# 7s_BMS_V1-1.net
KiCad netlist of a schematic drawn in EAGLE
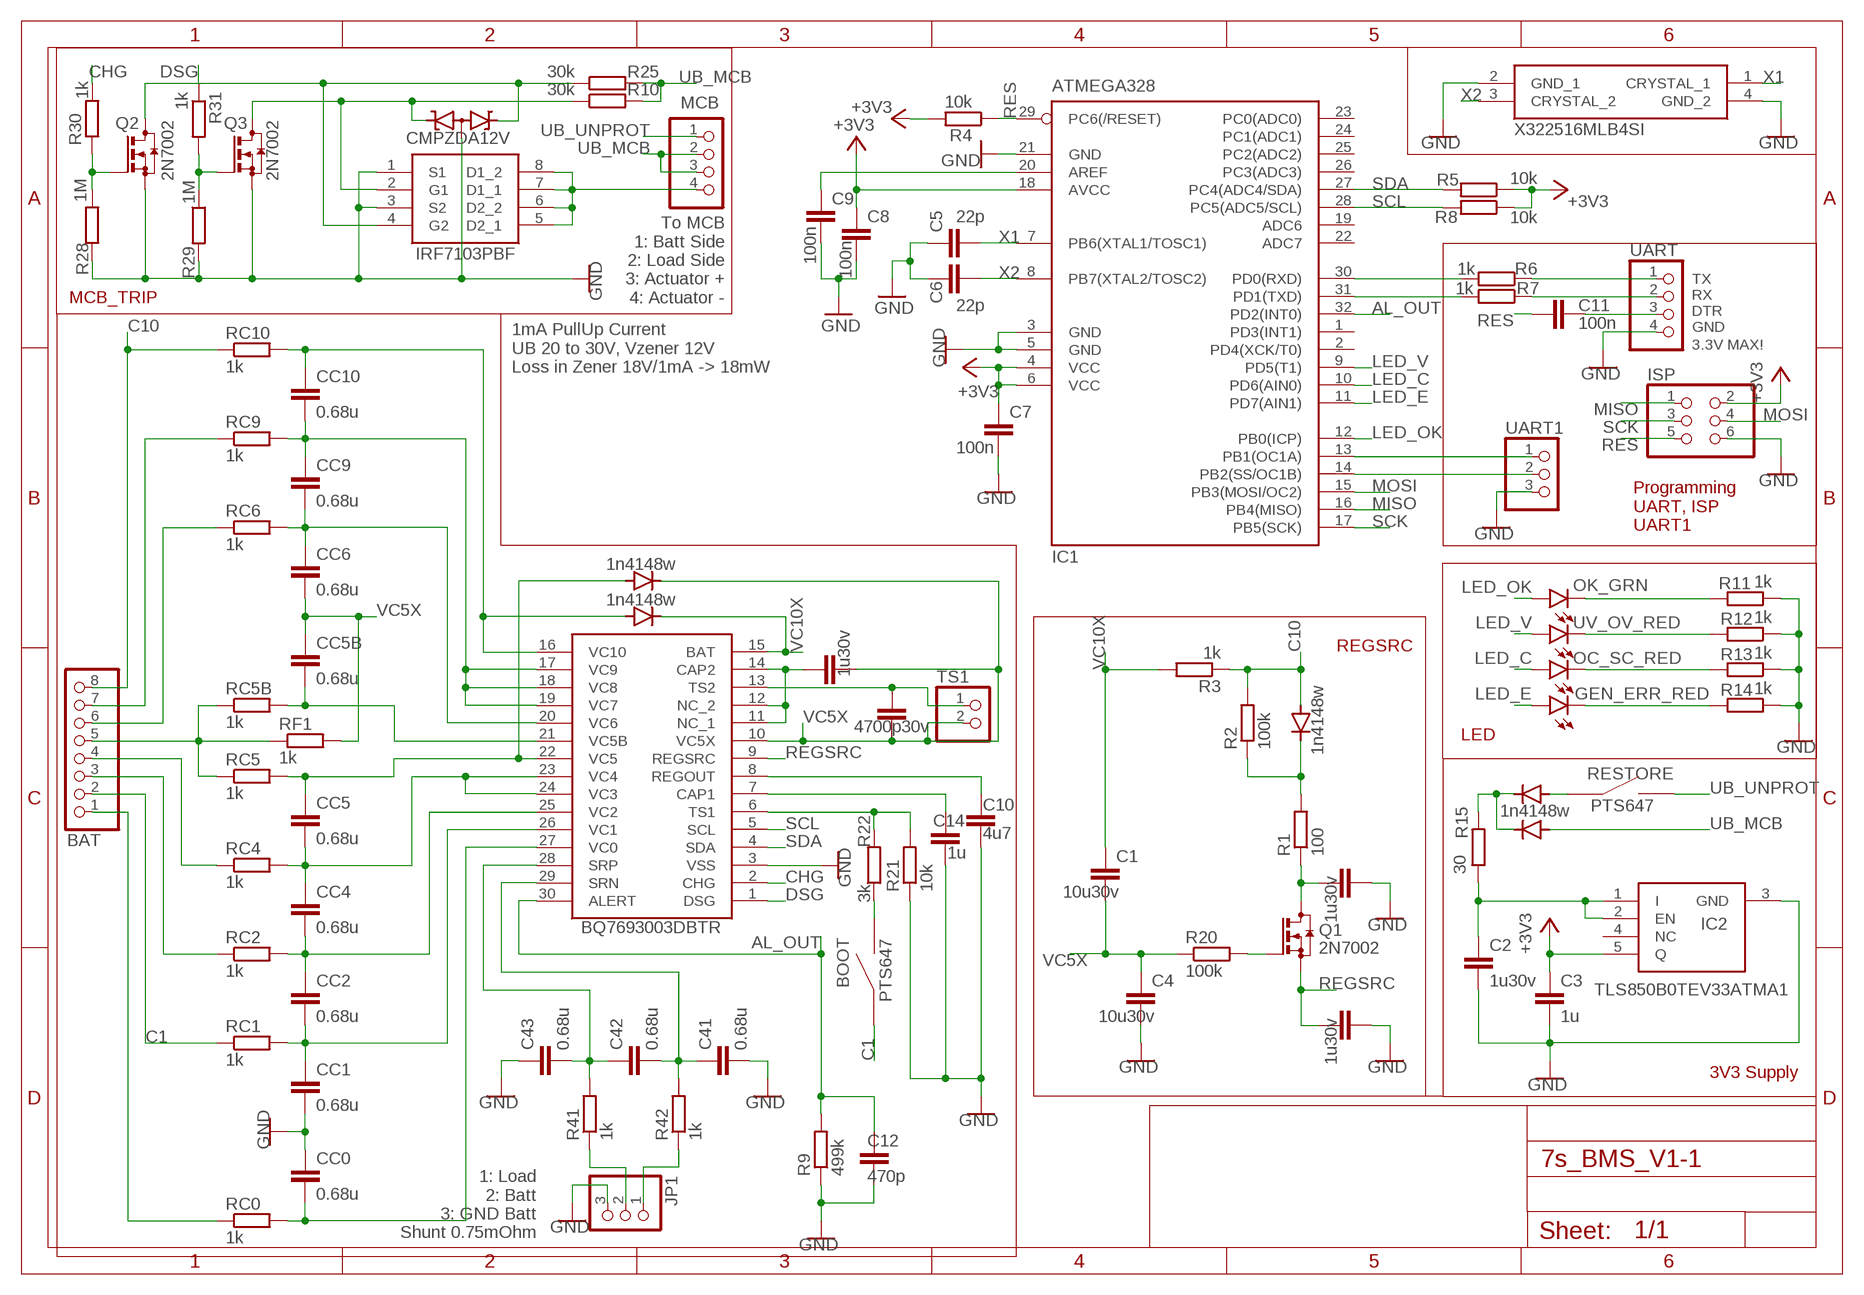
[diagram p0: schematic, sheet 1]

(export (version "E")
  (design (tool "Eeschema 10.0.6"))
  (components
    (comp (ref "BAT")
      (value "PINHD-1X8/90")
      (footprint "eagle-import:1X08_90")
      (libsource (lib "eagle-import") (part "PINHD-1X8/90"))
    )
    (comp (ref "C1")
      (value "10u30v")
      (footprint "eagle-import:C0805")
      (libsource (lib "eagle-import") (part "C-EUC0805"))
    )
    (comp (ref "C2")
      (value "1u30v")
      (footprint "eagle-import:C0805")
      (libsource (lib "eagle-import") (part "C-EUC0805"))
    )
    (comp (ref "C3")
      (value "1u")
      (footprint "eagle-import:C0603")
      (libsource (lib "eagle-import") (part "C-EUC0603"))
    )
    (comp (ref "C4")
      (value "10u30v")
      (footprint "eagle-import:C0805")
      (libsource (lib "eagle-import") (part "C-EUC0805"))
    )
    (comp (ref "C5")
      (value "22p")
      (footprint "eagle-import:C0603")
      (libsource (lib "eagle-import") (part "C-EUC0603"))
    )
    (comp (ref "C6")
      (value "22p")
      (footprint "eagle-import:C0603")
      (libsource (lib "eagle-import") (part "C-EUC0603"))
    )
    (comp (ref "C7")
      (value "100n")
      (footprint "eagle-import:C0603")
      (libsource (lib "eagle-import") (part "C-EUC0603"))
    )
    (comp (ref "C8")
      (value "100n")
      (footprint "eagle-import:C0603")
      (libsource (lib "eagle-import") (part "C-EUC0603"))
    )
    (comp (ref "C9")
      (value "100n")
      (footprint "eagle-import:C0603")
      (libsource (lib "eagle-import") (part "C-EUC0603"))
    )
    (comp (ref "C10")
      (value "4u7")
      (footprint "eagle-import:C0805")
      (libsource (lib "eagle-import") (part "C-EUC0805"))
    )
    (comp (ref "C11")
      (value "100n")
      (footprint "eagle-import:C0603")
      (libsource (lib "eagle-import") (part "C-EUC0603"))
    )
    (comp (ref "C12")
      (value "470p")
      (footprint "eagle-import:C0603")
      (libsource (lib "eagle-import") (part "C-EUC0603"))
    )
    (comp (ref "C14")
      (value "1u")
      (footprint "eagle-import:C0603")
      (libsource (lib "eagle-import") (part "C-EUC0603"))
    )
    (comp (ref "C30")
      (value "1u30v")
      (footprint "eagle-import:C0603")
      (libsource (lib "eagle-import") (part "C-EUC0603"))
    )
    (comp (ref "C31")
      (value "1u30v")
      (footprint "eagle-import:C0603")
      (libsource (lib "eagle-import") (part "C-EUC0603"))
    )
    (comp (ref "C41")
      (value "0.68u")
      (footprint "eagle-import:C0603")
      (libsource (lib "eagle-import") (part "C-EUC0603"))
    )
    (comp (ref "C42")
      (value "0.68u")
      (footprint "eagle-import:C0603")
      (libsource (lib "eagle-import") (part "C-EUC0603"))
    )
    (comp (ref "C43")
      (value "0.68u")
      (footprint "eagle-import:C0603")
      (libsource (lib "eagle-import") (part "C-EUC0603"))
    )
    (comp (ref "C61")
      (value "1u30v")
      (footprint "eagle-import:C0603")
      (libsource (lib "eagle-import") (part "C-EUC0603"))
    )
    (comp (ref "C62")
      (value "4700p30v")
      (footprint "eagle-import:C0603")
      (libsource (lib "eagle-import") (part "C-EUC0603"))
    )
    (comp (ref "CC0")
      (value "0.68u")
      (footprint "eagle-import:C0603")
      (libsource (lib "eagle-import") (part "C-EUC0603"))
    )
    (comp (ref "CC1")
      (value "0.68u")
      (footprint "eagle-import:C0603")
      (libsource (lib "eagle-import") (part "C-EUC0603"))
    )
    (comp (ref "CC2")
      (value "0.68u")
      (footprint "eagle-import:C0603")
      (libsource (lib "eagle-import") (part "C-EUC0603"))
    )
    (comp (ref "CC4")
      (value "0.68u")
      (footprint "eagle-import:C0603")
      (libsource (lib "eagle-import") (part "C-EUC0603"))
    )
    (comp (ref "CC5")
      (value "0.68u")
      (footprint "eagle-import:C0603")
      (libsource (lib "eagle-import") (part "C-EUC0603"))
    )
    (comp (ref "CC5B")
      (value "0.68u")
      (footprint "eagle-import:C0603")
      (libsource (lib "eagle-import") (part "C-EUC0603"))
    )
    (comp (ref "CC6")
      (value "0.68u")
      (footprint "eagle-import:C0603")
      (libsource (lib "eagle-import") (part "C-EUC0603"))
    )
    (comp (ref "CC9")
      (value "0.68u")
      (footprint "eagle-import:C0603")
      (libsource (lib "eagle-import") (part "C-EUC0603"))
    )
    (comp (ref "CC10")
      (value "0.68u")
      (footprint "eagle-import:C0603")
      (libsource (lib "eagle-import") (part "C-EUC0603"))
    )
    (comp (ref "D1")
      (value "1n4148w")
      (footprint "eagle-import:SOD123")
      (libsource (lib "eagle-import") (part "DIODE-SOD123"))
    )
    (comp (ref "D2")
      (value "1n4148w")
      (footprint "eagle-import:SOD123")
      (libsource (lib "eagle-import") (part "DIODE-SOD123"))
    )
    (comp (ref "D3")
      (value "1n4148w")
      (footprint "eagle-import:SOD123")
      (libsource (lib "eagle-import") (part "DIODE-SOD123"))
    )
    (comp (ref "D4")
      (value "1n4148w")
      (footprint "eagle-import:SOD123")
      (libsource (lib "eagle-import") (part "DIODE-SOD123"))
    )
    (comp (ref "D5")
      (value "1n4148w")
      (footprint "eagle-import:SOD123")
      (libsource (lib "eagle-import") (part "DIODE-SOD123"))
    )
    (comp (ref "GEN_ERR_RED")
      (value "KT-0603R")
      (footprint "eagle-import:CHIP-LED0603")
      (libsource (lib "eagle-import") (part "LEDCHIP-LED0603"))
    )
    (comp (ref "IC1")
      (value "ATMEGA328")
      (footprint "eagle-import:TQFP32-08")
      (fields (field (name "MPN") "ATMEGA8-16AU"))
      (libsource (lib "eagle-import") (part "MEGA8-AI"))
    )
    (comp (ref "IC2")
      (value "TLS850B0TEV33ATMA1")
      (footprint "eagle-import:BTS6143D")
      (fields (field (name "MOUSER_PART_NUMBER") "726-TLS850B0TEV33ATM"))
      (libsource (lib "eagle-import") (part "TLS850B0TEV33ATMA1"))
    )
    (comp (ref "IC3")
      (value "BQ7693003DBTR")
      (footprint "eagle-import:SOP50P640X120-30N")
      (fields (field (name "MOUSER_PART_NUMBER") "595-BQ7693003DBTR"))
      (libsource (lib "eagle-import") (part "BQ7693003DBTR"))
    )
    (comp (ref "ISP")
      (value "PINHD-2X3")
      (footprint "eagle-import:2X03")
      (libsource (lib "eagle-import") (part "PINHD-2X3"))
    )
    (comp (ref "JP1")
      (value "PINHD-1X3/90")
      (footprint "eagle-import:1X03_90")
      (libsource (lib "eagle-import") (part "PINHD-1X3/90"))
    )
    (comp (ref "MCB")
      (value "PINHD-1X4")
      (footprint "eagle-import:1X04")
      (libsource (lib "eagle-import") (part "PINHD-1X4"))
    )
    (comp (ref "OC_SC_RED")
      (value "KT-0603R")
      (footprint "eagle-import:CHIP-LED0603")
      (libsource (lib "eagle-import") (part "LEDCHIP-LED0603"))
    )
    (comp (ref "OK_GRN")
      (value "19-217/GHC-YR1S2/3T")
      (footprint "eagle-import:CHIP-LED0603")
      (libsource (lib "eagle-import") (part "LEDCHIP-LED0603"))
    )
    (comp (ref "Q1")
      (value "2N7002")
      (footprint "eagle-import:SOT23")
      (libsource (lib "eagle-import") (part "BSS123"))
    )
    (comp (ref "Q2")
      (value "2N7002")
      (footprint "eagle-import:SOT23")
      (libsource (lib "eagle-import") (part "BSS123"))
    )
    (comp (ref "Q3")
      (value "2N7002")
      (footprint "eagle-import:SOT23")
      (libsource (lib "eagle-import") (part "BSS123"))
    )
    (comp (ref "Q4")
      (value "IRF7103PBF")
      (footprint "eagle-import:SOIC127P600X175-8N")
      (libsource (lib "eagle-import") (part "IRF7103PBF"))
    )
    (comp (ref "R1")
      (value "100")
      (footprint "eagle-import:R0603")
      (libsource (lib "eagle-import") (part "R-EU_R0603"))
    )
    (comp (ref "R2")
      (value "100k")
      (footprint "eagle-import:R0603")
      (libsource (lib "eagle-import") (part "R-EU_R0603"))
    )
    (comp (ref "R3")
      (value "1k")
      (footprint "eagle-import:R0603")
      (libsource (lib "eagle-import") (part "R-EU_R0603"))
    )
    (comp (ref "R4")
      (value "10k")
      (footprint "eagle-import:R0603")
      (libsource (lib "eagle-import") (part "R-EU_R0603"))
    )
    (comp (ref "R5")
      (value "10k")
      (footprint "eagle-import:R0603")
      (libsource (lib "eagle-import") (part "R-EU_R0603"))
    )
    (comp (ref "R6")
      (value "1k")
      (footprint "eagle-import:R0603")
      (libsource (lib "eagle-import") (part "R-EU_R0603"))
    )
    (comp (ref "R7")
      (value "1k")
      (footprint "eagle-import:R0603")
      (libsource (lib "eagle-import") (part "R-EU_R0603"))
    )
    (comp (ref "R8")
      (value "10k")
      (footprint "eagle-import:R0603")
      (libsource (lib "eagle-import") (part "R-EU_R0603"))
    )
    (comp (ref "R9")
      (value "499k")
      (footprint "eagle-import:R0603")
      (libsource (lib "eagle-import") (part "R-EU_R0603"))
    )
    (comp (ref "R10")
      (value "30k")
      (footprint "eagle-import:R0603")
      (libsource (lib "eagle-import") (part "R-EU_R0603"))
    )
    (comp (ref "R11")
      (value "1k")
      (footprint "eagle-import:R0603")
      (libsource (lib "eagle-import") (part "R-EU_R0603"))
    )
    (comp (ref "R12")
      (value "1k")
      (footprint "eagle-import:R0603")
      (libsource (lib "eagle-import") (part "R-EU_R0603"))
    )
    (comp (ref "R13")
      (value "1k")
      (footprint "eagle-import:R0603")
      (libsource (lib "eagle-import") (part "R-EU_R0603"))
    )
    (comp (ref "R14")
      (value "1k")
      (footprint "eagle-import:R0603")
      (libsource (lib "eagle-import") (part "R-EU_R0603"))
    )
    (comp (ref "R15")
      (value "30")
      (footprint "eagle-import:R0805")
      (libsource (lib "eagle-import") (part "R-EU_R0805"))
    )
    (comp (ref "R20")
      (value "100k")
      (footprint "eagle-import:R0603")
      (libsource (lib "eagle-import") (part "R-EU_R0603"))
    )
    (comp (ref "R21")
      (value "10k")
      (footprint "eagle-import:R0603")
      (libsource (lib "eagle-import") (part "R-EU_R0603"))
    )
    (comp (ref "R22")
      (value "3k")
      (footprint "eagle-import:R0603")
      (libsource (lib "eagle-import") (part "R-EU_R0603"))
    )
    (comp (ref "R25")
      (value "30k")
      (footprint "eagle-import:R0603")
      (libsource (lib "eagle-import") (part "R-EU_R0603"))
    )
    (comp (ref "R28")
      (value "1M")
      (footprint "eagle-import:R0603")
      (libsource (lib "eagle-import") (part "R-EU_R0603"))
    )
    (comp (ref "R29")
      (value "1M")
      (footprint "eagle-import:R0603")
      (libsource (lib "eagle-import") (part "R-EU_R0603"))
    )
    (comp (ref "R30")
      (value "1k")
      (footprint "eagle-import:R0603")
      (libsource (lib "eagle-import") (part "R-EU_R0603"))
    )
    (comp (ref "R31")
      (value "1k")
      (footprint "eagle-import:R0603")
      (libsource (lib "eagle-import") (part "R-EU_R0603"))
    )
    (comp (ref "R41")
      (value "1k")
      (footprint "eagle-import:R0603")
      (libsource (lib "eagle-import") (part "R-EU_R0603"))
    )
    (comp (ref "R42")
      (value "1k")
      (footprint "eagle-import:R0603")
      (libsource (lib "eagle-import") (part "R-EU_R0603"))
    )
    (comp (ref "RC0")
      (value "1k")
      (footprint "eagle-import:R0603")
      (libsource (lib "eagle-import") (part "R-EU_R0603"))
    )
    (comp (ref "RC1")
      (value "1k")
      (footprint "eagle-import:R0603")
      (libsource (lib "eagle-import") (part "R-EU_R0603"))
    )
    (comp (ref "RC2")
      (value "1k")
      (footprint "eagle-import:R0603")
      (libsource (lib "eagle-import") (part "R-EU_R0603"))
    )
    (comp (ref "RC4")
      (value "1k")
      (footprint "eagle-import:R0603")
      (libsource (lib "eagle-import") (part "R-EU_R0603"))
    )
    (comp (ref "RC5")
      (value "1k")
      (footprint "eagle-import:R0603")
      (libsource (lib "eagle-import") (part "R-EU_R0603"))
    )
    (comp (ref "RC5B")
      (value "1k")
      (footprint "eagle-import:R0603")
      (libsource (lib "eagle-import") (part "R-EU_R0603"))
    )
    (comp (ref "RC6")
      (value "1k")
      (footprint "eagle-import:R0603")
      (libsource (lib "eagle-import") (part "R-EU_R0603"))
    )
    (comp (ref "RC9")
      (value "1k")
      (footprint "eagle-import:R0603")
      (libsource (lib "eagle-import") (part "R-EU_R0603"))
    )
    (comp (ref "RC10")
      (value "1k")
      (footprint "eagle-import:R0603")
      (libsource (lib "eagle-import") (part "R-EU_R0603"))
    )
    (comp (ref "RF1")
      (value "1k")
      (footprint "eagle-import:R0603")
      (libsource (lib "eagle-import") (part "R-EU_R0603"))
    )
    (comp (ref "TS1")
      (value "PINHD-1X2/90")
      (footprint "eagle-import:1X02_90")
      (libsource (lib "eagle-import") (part "PINHD-1X2/90"))
    )
    (comp (ref "U$1")
      (value "PTS647")
      (footprint "eagle-import:PTS647")
      (libsource (lib "eagle-import") (part "PTS647"))
    )
    (comp (ref "U$2")
      (value "PTS647")
      (footprint "eagle-import:PTS647")
      (libsource (lib "eagle-import") (part "PTS647"))
    )
    (comp (ref "U$3")
      (value "CMPZDA12V")
      (footprint "eagle-import:SOT23")
      (libsource (lib "eagle-import") (part "CMPZDA12V"))
    )
    (comp (ref "UART")
      (value "PINHD-1X4")
      (footprint "eagle-import:1X04")
      (libsource (lib "eagle-import") (part "PINHD-1X4"))
    )
    (comp (ref "UART1")
      (value "PINHD-1X3")
      (footprint "eagle-import:1X03")
      (libsource (lib "eagle-import") (part "PINHD-1X3"))
    )
    (comp (ref "UV_OV_RED")
      (value "KT-0603R")
      (footprint "eagle-import:CHIP-LED0603")
      (libsource (lib "eagle-import") (part "LEDCHIP-LED0603"))
    )
    (comp (ref "Y1")
      (value "X322516MLB4SI")
      (footprint "eagle-import:X322516MLB4SI")
      (libsource (lib "eagle-import") (part "X322516MLB4SI"))
    )
  )
  (nets
    (net (code "1") (name "+3V3") (class "Default")
      (node (ref "C3") (pin "1") (pinfunction "1_1") (pintype "passive"))
      (node (ref "C7") (pin "1") (pinfunction "1_1") (pintype "passive"))
      (node (ref "C8") (pin "1") (pinfunction "1_1") (pintype "passive"))
      (node (ref "IC1") (pin "18") (pinfunction "AVCC_18") (pintype "power_in"))
      (node (ref "IC1") (pin "4") (pinfunction "VCC_4") (pintype "power_in"))
      (node (ref "IC1") (pin "6") (pinfunction "VCC_6") (pintype "power_in"))
      (node (ref "IC2") (pin "5") (pinfunction "Q_5") (pintype "bidirectional"))
      (node (ref "ISP") (pin "2") (pinfunction "2_2") (pintype "passive"))
      (node (ref "R4") (pin "2") (pinfunction "2_2") (pintype "passive"))
      (node (ref "R5") (pin "1") (pinfunction "1_1") (pintype "passive"))
      (node (ref "R8") (pin "1") (pinfunction "1_1") (pintype "passive"))
    )
    (net (code "2") (name "/AL_OUT") (class "Default")
      (node (ref "C12") (pin "1") (pinfunction "1_1") (pintype "passive"))
      (node (ref "IC1") (pin "32") (pinfunction "PD2(INT0)_32") (pintype "bidirectional"))
      (node (ref "IC3") (pin "30") (pinfunction "ALERT_30") (pintype "bidirectional"))
      (node (ref "R9") (pin "2") (pinfunction "2_2") (pintype "passive"))
    )
    (net (code "3") (name "/C1") (class "Default")
      (node (ref "BAT") (pin "2") (pinfunction "2_2") (pintype "passive"))
      (node (ref "RC1") (pin "1") (pinfunction "1_1") (pintype "passive"))
      (node (ref "U$2") (pin "1") (pinfunction "P$1_1") (pintype "bidirectional"))
      (node (ref "U$2") (pin "2") (pinfunction "P$1_2") (pintype "bidirectional"))
    )
    (net (code "4") (name "/C10") (class "Default")
      (node (ref "BAT") (pin "8") (pinfunction "8_8") (pintype "passive"))
      (node (ref "D5") (pin "A") (pinfunction "A_A") (pintype "passive"))
      (node (ref "R2") (pin "2") (pinfunction "2_2") (pintype "passive"))
      (node (ref "R3") (pin "1") (pinfunction "1_1") (pintype "passive"))
      (node (ref "RC10") (pin "1") (pinfunction "1_1") (pintype "passive"))
    )
    (net (code "5") (name "/CHG") (class "Default")
      (node (ref "IC3") (pin "2") (pinfunction "CHG_2") (pintype "bidirectional"))
      (node (ref "R30") (pin "2") (pinfunction "2_2") (pintype "passive"))
    )
    (net (code "6") (name "/DSG") (class "Default")
      (node (ref "IC3") (pin "1") (pinfunction "DSG_1") (pintype "bidirectional"))
      (node (ref "R31") (pin "1") (pinfunction "1_1") (pintype "passive"))
    )
    (net (code "7") (name "/LED_C") (class "Default")
      (node (ref "IC1") (pin "10") (pinfunction "PD6(AIN0)_10") (pintype "bidirectional"))
      (node (ref "OC_SC_RED") (pin "A") (pinfunction "A_A") (pintype "passive"))
    )
    (net (code "8") (name "/LED_E") (class "Default")
      (node (ref "GEN_ERR_RED") (pin "A") (pinfunction "A_A") (pintype "passive"))
      (node (ref "IC1") (pin "11") (pinfunction "PD7(AIN1)_11") (pintype "bidirectional"))
    )
    (net (code "9") (name "/LED_OK") (class "Default")
      (node (ref "IC1") (pin "12") (pinfunction "PB0(ICP)_12") (pintype "bidirectional"))
      (node (ref "OK_GRN") (pin "A") (pinfunction "A_A") (pintype "passive"))
    )
    (net (code "10") (name "/LED_V") (class "Default")
      (node (ref "IC1") (pin "9") (pinfunction "PD5(T1)_9") (pintype "bidirectional"))
      (node (ref "UV_OV_RED") (pin "A") (pinfunction "A_A") (pintype "passive"))
    )
    (net (code "11") (name "/MISO") (class "Default")
      (node (ref "IC1") (pin "16") (pinfunction "PB4(MISO)_16") (pintype "bidirectional"))
      (node (ref "ISP") (pin "1") (pinfunction "1_1") (pintype "passive"))
    )
    (net (code "12") (name "/MOSI") (class "Default")
      (node (ref "IC1") (pin "15") (pinfunction "PB3(MOSI/OC2)_15") (pintype "bidirectional"))
      (node (ref "ISP") (pin "4") (pinfunction "4_4") (pintype "passive"))
    )
    (net (code "13") (name "/REGSRC") (class "Default")
      (node (ref "C31") (pin "2") (pinfunction "2_2") (pintype "passive"))
      (node (ref "IC3") (pin "9") (pinfunction "REGSRC_9") (pintype "bidirectional"))
      (node (ref "Q1") (pin "2") (pinfunction "S_2") (pintype "passive"))
    )
    (net (code "14") (name "/RES") (class "Default")
      (node (ref "C11") (pin "1") (pinfunction "1_1") (pintype "passive"))
      (node (ref "IC1") (pin "29") (pinfunction "PC6(/RESET)_29") (pintype "bidirectional"))
      (node (ref "ISP") (pin "5") (pinfunction "5_5") (pintype "passive"))
      (node (ref "R4") (pin "1") (pinfunction "1_1") (pintype "passive"))
    )
    (net (code "15") (name "/SCK") (class "Default")
      (node (ref "IC1") (pin "17") (pinfunction "PB5(SCK)_17") (pintype "bidirectional"))
      (node (ref "ISP") (pin "3") (pinfunction "3_3") (pintype "passive"))
    )
    (net (code "16") (name "/SCL") (class "Default")
      (node (ref "IC1") (pin "28") (pinfunction "PC5(ADC5/SCL)_28") (pintype "bidirectional"))
      (node (ref "IC3") (pin "5") (pinfunction "SCL_5") (pintype "bidirectional"))
      (node (ref "R8") (pin "2") (pinfunction "2_2") (pintype "passive"))
    )
    (net (code "17") (name "/SDA") (class "Default")
      (node (ref "IC1") (pin "27") (pinfunction "PC4(ADC4/SDA)_27") (pintype "bidirectional"))
      (node (ref "IC3") (pin "4") (pinfunction "SDA_4") (pintype "bidirectional"))
      (node (ref "R5") (pin "2") (pinfunction "2_2") (pintype "passive"))
    )
    (net (code "18") (name "/UB_MCB") (class "Default")
      (node (ref "D1") (pin "A") (pinfunction "A_A") (pintype "passive"))
      (node (ref "MCB") (pin "2") (pinfunction "2_2") (pintype "passive"))
      (node (ref "MCB") (pin "3") (pinfunction "3_3") (pintype "passive"))
      (node (ref "R10") (pin "2") (pinfunction "2_2") (pintype "passive"))
      (node (ref "R25") (pin "2") (pinfunction "2_2") (pintype "passive"))
    )
    (net (code "19") (name "/UB_UNPROT") (class "Default")
      (node (ref "MCB") (pin "1") (pinfunction "1_1") (pintype "passive"))
      (node (ref "U$1") (pin "3") (pinfunction "P$2_3") (pintype "bidirectional"))
      (node (ref "U$1") (pin "4") (pinfunction "P$2_4") (pintype "bidirectional"))
    )
    (net (code "20") (name "/VC5X") (class "Default")
      (node (ref "C1") (pin "2") (pinfunction "2_2") (pintype "passive"))
      (node (ref "C4") (pin "1") (pinfunction "1_1") (pintype "passive"))
      (node (ref "C61") (pin "2") (pinfunction "2_2") (pintype "passive"))
      (node (ref "C62") (pin "1") (pinfunction "1_1") (pintype "passive"))
      (node (ref "CC5B") (pin "1") (pinfunction "1_1") (pintype "passive"))
      (node (ref "CC6") (pin "2") (pinfunction "2_2") (pintype "passive"))
      (node (ref "D4") (pin "C") (pinfunction "C_C") (pintype "passive"))
      (node (ref "IC3") (pin "10") (pinfunction "VC5X_10") (pintype "bidirectional"))
      (node (ref "R20") (pin "1") (pinfunction "1_1") (pintype "passive"))
      (node (ref "RF1") (pin "2") (pinfunction "2_2") (pintype "passive"))
      (node (ref "TS1") (pin "2") (pinfunction "2_2") (pintype "passive"))
    )
    (net (code "21") (name "/VC10X") (class "Default")
      (node (ref "C1") (pin "1") (pinfunction "1_1") (pintype "passive"))
      (node (ref "D3") (pin "C") (pinfunction "C_C") (pintype "passive"))
      (node (ref "IC3") (pin "15") (pinfunction "BAT_15") (pintype "bidirectional"))
      (node (ref "R3") (pin "2") (pinfunction "2_2") (pintype "passive"))
    )
    (net (code "22") (name "/X1") (class "Default")
      (node (ref "C5") (pin "2") (pinfunction "2_2") (pintype "passive"))
      (node (ref "IC1") (pin "7") (pinfunction "PB6(XTAL1/TOSC1)_7") (pintype "bidirectional"))
      (node (ref "Y1") (pin "1") (pinfunction "CRYSTAL_1_1") (pintype "bidirectional"))
    )
    (net (code "23") (name "/X2") (class "Default")
      (node (ref "C6") (pin "2") (pinfunction "2_2") (pintype "passive"))
      (node (ref "IC1") (pin "8") (pinfunction "PB7(XTAL2/TOSC2)_8") (pintype "bidirectional"))
      (node (ref "Y1") (pin "3") (pinfunction "CRYSTAL_2_3") (pintype "bidirectional"))
    )
    (net (code "24") (name "GND") (class "Default")
      (node (ref "C10") (pin "2") (pinfunction "2_2") (pintype "passive"))
      (node (ref "C12") (pin "2") (pinfunction "2_2") (pintype "passive"))
      (node (ref "C14") (pin "2") (pinfunction "2_2") (pintype "passive"))
      (node (ref "C2") (pin "2") (pinfunction "2_2") (pintype "passive"))
      (node (ref "C3") (pin "2") (pinfunction "2_2") (pintype "passive"))
      (node (ref "C30") (pin "1") (pinfunction "1_1") (pintype "passive"))
      (node (ref "C31") (pin "1") (pinfunction "1_1") (pintype "passive"))
      (node (ref "C4") (pin "2") (pinfunction "2_2") (pintype "passive"))
      (node (ref "C41") (pin "2") (pinfunction "2_2") (pintype "passive"))
      (node (ref "C43") (pin "1") (pinfunction "1_1") (pintype "passive"))
      (node (ref "C5") (pin "1") (pinfunction "1_1") (pintype "passive"))
      (node (ref "C6") (pin "1") (pinfunction "1_1") (pintype "passive"))
      (node (ref "C7") (pin "2") (pinfunction "2_2") (pintype "passive"))
      (node (ref "C8") (pin "2") (pinfunction "2_2") (pintype "passive"))
      (node (ref "C9") (pin "2") (pinfunction "2_2") (pintype "passive"))
      (node (ref "CC0") (pin "1") (pinfunction "1_1") (pintype "passive"))
      (node (ref "CC1") (pin "2") (pinfunction "2_2") (pintype "passive"))
      (node (ref "IC1") (pin "21") (pinfunction "GND_21") (pintype "power_in"))
      (node (ref "IC1") (pin "3") (pinfunction "GND_3") (pintype "power_in"))
      (node (ref "IC1") (pin "5") (pinfunction "GND_5") (pintype "power_in"))
      (node (ref "IC2") (pin "3") (pinfunction "GND_3") (pintype "bidirectional"))
      (node (ref "IC3") (pin "3") (pinfunction "VSS_3") (pintype "bidirectional"))
      (node (ref "ISP") (pin "6") (pinfunction "6_6") (pintype "passive"))
      (node (ref "JP1") (pin "3") (pinfunction "3_3") (pintype "passive"))
      (node (ref "Q2") (pin "2") (pinfunction "S_2") (pintype "passive"))
      (node (ref "Q3") (pin "2") (pinfunction "S_2") (pintype "passive"))
      (node (ref "Q4") (pin "1") (pinfunction "S1_1") (pintype "bidirectional"))
      (node (ref "Q4") (pin "3") (pinfunction "S2_3") (pintype "bidirectional"))
      (node (ref "R11") (pin "1") (pinfunction "1_1") (pintype "passive"))
      (node (ref "R12") (pin "1") (pinfunction "1_1") (pintype "passive"))
      (node (ref "R13") (pin "1") (pinfunction "1_1") (pintype "passive"))
      (node (ref "R14") (pin "1") (pinfunction "1_1") (pintype "passive"))
      (node (ref "R21") (pin "1") (pinfunction "1_1") (pintype "passive"))
      (node (ref "R28") (pin "1") (pinfunction "1_1") (pintype "passive"))
      (node (ref "R29") (pin "2") (pinfunction "2_2") (pintype "passive"))
      (node (ref "R9") (pin "1") (pinfunction "1_1") (pintype "passive"))
      (node (ref "U$3") (pin "3") (pinfunction "A_3") (pintype "passive"))
      (node (ref "UART") (pin "4") (pinfunction "4_4") (pintype "passive"))
      (node (ref "UART1") (pin "3") (pinfunction "3_3") (pintype "passive"))
      (node (ref "Y1") (pin "2") (pinfunction "GND_1_2") (pintype "bidirectional"))
      (node (ref "Y1") (pin "4") (pinfunction "GND_2_4") (pintype "bidirectional"))
    )
    (net (code "25") (name "Net-(BAT-Pad1)") (class "Default")
      (node (ref "BAT") (pin "1") (pinfunction "1_1") (pintype "passive"))
      (node (ref "RC0") (pin "1") (pinfunction "1_1") (pintype "passive"))
    )
    (net (code "26") (name "Net-(BAT-Pad3)") (class "Default")
      (node (ref "BAT") (pin "3") (pinfunction "3_3") (pintype "passive"))
      (node (ref "RC2") (pin "1") (pinfunction "1_1") (pintype "passive"))
    )
    (net (code "27") (name "Net-(BAT-Pad4)") (class "Default")
      (node (ref "BAT") (pin "4") (pinfunction "4_4") (pintype "passive"))
      (node (ref "RC4") (pin "1") (pinfunction "1_1") (pintype "passive"))
    )
    (net (code "28") (name "Net-(BAT-Pad5)") (class "Default")
      (node (ref "BAT") (pin "5") (pinfunction "5_5") (pintype "passive"))
      (node (ref "RC5") (pin "1") (pinfunction "1_1") (pintype "passive"))
      (node (ref "RC5B") (pin "1") (pinfunction "1_1") (pintype "passive"))
      (node (ref "RF1") (pin "1") (pinfunction "1_1") (pintype "passive"))
    )
    (net (code "29") (name "Net-(BAT-Pad6)") (class "Default")
      (node (ref "BAT") (pin "6") (pinfunction "6_6") (pintype "passive"))
      (node (ref "RC6") (pin "1") (pinfunction "1_1") (pintype "passive"))
    )
    (net (code "30") (name "Net-(BAT-Pad7)") (class "Default")
      (node (ref "BAT") (pin "7") (pinfunction "7_7") (pintype "passive"))
      (node (ref "RC9") (pin "1") (pinfunction "1_1") (pintype "passive"))
    )
    (net (code "31") (name "Net-(C11-Pad2)") (class "Default")
      (node (ref "C11") (pin "2") (pinfunction "2_2") (pintype "passive"))
      (node (ref "UART") (pin "3") (pinfunction "3_3") (pintype "passive"))
    )
    (net (code "32") (name "Net-(D1-PadC)") (class "Default")
      (node (ref "D1") (pin "C") (pinfunction "C_C") (pintype "passive"))
      (node (ref "D2") (pin "C") (pinfunction "C_C") (pintype "passive"))
      (node (ref "R15") (pin "2") (pinfunction "2_2") (pintype "passive"))
    )
    (net (code "33") (name "Net-(D2-PadA)") (class "Default")
      (node (ref "D2") (pin "A") (pinfunction "A_A") (pintype "passive"))
      (node (ref "U$1") (pin "1") (pinfunction "P$1_1") (pintype "bidirectional"))
      (node (ref "U$1") (pin "2") (pinfunction "P$1_2") (pintype "bidirectional"))
    )
    (net (code "34") (name "Net-(D5-PadC)") (class "Default")
      (node (ref "D5") (pin "C") (pinfunction "C_C") (pintype "passive"))
      (node (ref "R1") (pin "2") (pinfunction "2_2") (pintype "passive"))
      (node (ref "R2") (pin "1") (pinfunction "1_1") (pintype "passive"))
    )
    (net (code "35") (name "Net-(GEN_ERR_RED-PadC)") (class "Default")
      (node (ref "GEN_ERR_RED") (pin "C") (pinfunction "C_C") (pintype "passive"))
      (node (ref "R14") (pin "2") (pinfunction "2_2") (pintype "passive"))
    )
    (net (code "36") (name "Net-(IC1-AREF)") (class "Default")
      (node (ref "C9") (pin "1") (pinfunction "1_1") (pintype "passive"))
      (node (ref "IC1") (pin "20") (pinfunction "AREF_20") (pintype "passive"))
    )
    (net (code "37") (name "Net-(IC1-PB1(OC1A))") (class "Default")
      (node (ref "IC1") (pin "13") (pinfunction "PB1(OC1A)_13") (pintype "bidirectional"))
      (node (ref "UART1") (pin "1") (pinfunction "1_1") (pintype "passive"))
    )
    (net (code "38") (name "Net-(IC1-PB2(SS{slash}OC1B))") (class "Default")
      (node (ref "IC1") (pin "14") (pinfunction "PB2(SS/OC1B)_14") (pintype "bidirectional"))
      (node (ref "UART1") (pin "2") (pinfunction "2_2") (pintype "passive"))
    )
    (net (code "39") (name "Net-(IC1-PD0(RXD))") (class "Default")
      (node (ref "IC1") (pin "30") (pinfunction "PD0(RXD)_30") (pintype "bidirectional"))
      (node (ref "R6") (pin "2") (pinfunction "2_2") (pintype "passive"))
    )
    (net (code "40") (name "Net-(IC1-PD1(TXD))") (class "Default")
      (node (ref "IC1") (pin "31") (pinfunction "PD1(TXD)_31") (pintype "bidirectional"))
      (node (ref "R7") (pin "2") (pinfunction "2_2") (pintype "passive"))
    )
    (net (code "41") (name "Net-(IC2-EN)") (class "Default")
      (node (ref "C2") (pin "1") (pinfunction "1_1") (pintype "passive"))
      (node (ref "IC2") (pin "1") (pinfunction "I_1") (pintype "bidirectional"))
      (node (ref "IC2") (pin "2") (pinfunction "EN_2") (pintype "bidirectional"))
      (node (ref "R15") (pin "1") (pinfunction "1_1") (pintype "passive"))
    )
    (net (code "42") (name "Net-(IC3-CAP1)") (class "Default")
      (node (ref "C14") (pin "1") (pinfunction "1_1") (pintype "passive"))
      (node (ref "IC3") (pin "7") (pinfunction "CAP1_7") (pintype "bidirectional"))
    )
    (net (code "43") (name "Net-(IC3-CAP2)") (class "Default")
      (node (ref "C61") (pin "1") (pinfunction "1_1") (pintype "passive"))
      (node (ref "IC3") (pin "11") (pinfunction "NC_1_11") (pintype "bidirectional"))
      (node (ref "IC3") (pin "12") (pinfunction "NC_2_12") (pintype "bidirectional"))
      (node (ref "IC3") (pin "14") (pinfunction "CAP2_14") (pintype "bidirectional"))
    )
    (net (code "44") (name "Net-(IC3-REGOUT)") (class "Default")
      (node (ref "C10") (pin "1") (pinfunction "1_1") (pintype "passive"))
      (node (ref "IC3") (pin "8") (pinfunction "REGOUT_8") (pintype "bidirectional"))
    )
    (net (code "45") (name "Net-(IC3-SRN)") (class "Default")
      (node (ref "C41") (pin "1") (pinfunction "1_1") (pintype "passive"))
      (node (ref "C42") (pin "2") (pinfunction "2_2") (pintype "passive"))
      (node (ref "IC3") (pin "29") (pinfunction "SRN_29") (pintype "bidirectional"))
      (node (ref "R42") (pin "2") (pinfunction "2_2") (pintype "passive"))
    )
    (net (code "46") (name "Net-(IC3-SRP)") (class "Default")
      (node (ref "C42") (pin "1") (pinfunction "1_1") (pintype "passive"))
      (node (ref "C43") (pin "2") (pinfunction "2_2") (pintype "passive"))
      (node (ref "IC3") (pin "28") (pinfunction "SRP_28") (pintype "bidirectional"))
      (node (ref "R41") (pin "2") (pinfunction "2_2") (pintype "passive"))
    )
    (net (code "47") (name "Net-(IC3-TS1)") (class "Default")
      (node (ref "IC3") (pin "6") (pinfunction "TS1_6") (pintype "bidirectional"))
      (node (ref "R21") (pin "2") (pinfunction "2_2") (pintype "passive"))
      (node (ref "R22") (pin "2") (pinfunction "2_2") (pintype "passive"))
    )
    (net (code "48") (name "Net-(IC3-TS2)") (class "Default")
      (node (ref "C62") (pin "2") (pinfunction "2_2") (pintype "passive"))
      (node (ref "IC3") (pin "13") (pinfunction "TS2_13") (pintype "bidirectional"))
      (node (ref "TS1") (pin "1") (pinfunction "1_1") (pintype "passive"))
    )
    (net (code "49") (name "Net-(IC3-VC0)") (class "Default")
      (node (ref "CC0") (pin "2") (pinfunction "2_2") (pintype "passive"))
      (node (ref "IC3") (pin "27") (pinfunction "VC0_27") (pintype "bidirectional"))
      (node (ref "RC0") (pin "2") (pinfunction "2_2") (pintype "passive"))
    )
    (net (code "50") (name "Net-(IC3-VC1)") (class "Default")
      (node (ref "CC1") (pin "1") (pinfunction "1_1") (pintype "passive"))
      (node (ref "CC2") (pin "2") (pinfunction "2_2") (pintype "passive"))
      (node (ref "IC3") (pin "26") (pinfunction "VC1_26") (pintype "bidirectional"))
      (node (ref "RC1") (pin "2") (pinfunction "2_2") (pintype "passive"))
    )
    (net (code "51") (name "Net-(IC3-VC2)") (class "Default")
      (node (ref "CC2") (pin "1") (pinfunction "1_1") (pintype "passive"))
      (node (ref "CC4") (pin "2") (pinfunction "2_2") (pintype "passive"))
      (node (ref "IC3") (pin "25") (pinfunction "VC2_25") (pintype "bidirectional"))
      (node (ref "RC2") (pin "2") (pinfunction "2_2") (pintype "passive"))
    )
    (net (code "52") (name "Net-(IC3-VC3)") (class "Default")
      (node (ref "CC4") (pin "1") (pinfunction "1_1") (pintype "passive"))
      (node (ref "CC5") (pin "2") (pinfunction "2_2") (pintype "passive"))
      (node (ref "IC3") (pin "23") (pinfunction "VC4_23") (pintype "bidirectional"))
      (node (ref "IC3") (pin "24") (pinfunction "VC3_24") (pintype "bidirectional"))
      (node (ref "RC4") (pin "2") (pinfunction "2_2") (pintype "passive"))
    )
    (net (code "53") (name "Net-(IC3-VC5)") (class "Default")
      (node (ref "CC5") (pin "1") (pinfunction "1_1") (pintype "passive"))
      (node (ref "D4") (pin "A") (pinfunction "A_A") (pintype "passive"))
      (node (ref "IC3") (pin "22") (pinfunction "VC5_22") (pintype "bidirectional"))
      (node (ref "RC5") (pin "2") (pinfunction "2_2") (pintype "passive"))
    )
    (net (code "54") (name "Net-(IC3-VC5B)") (class "Default")
      (node (ref "CC5B") (pin "2") (pinfunction "2_2") (pintype "passive"))
      (node (ref "IC3") (pin "21") (pinfunction "VC5B_21") (pintype "bidirectional"))
      (node (ref "RC5B") (pin "2") (pinfunction "2_2") (pintype "passive"))
    )
    (net (code "55") (name "Net-(IC3-VC6)") (class "Default")
      (node (ref "CC6") (pin "1") (pinfunction "1_1") (pintype "passive"))
      (node (ref "CC9") (pin "2") (pinfunction "2_2") (pintype "passive"))
      (node (ref "IC3") (pin "20") (pinfunction "VC6_20") (pintype "bidirectional"))
      (node (ref "RC6") (pin "2") (pinfunction "2_2") (pintype "passive"))
    )
    (net (code "56") (name "Net-(IC3-VC7)") (class "Default")
      (node (ref "CC10") (pin "2") (pinfunction "2_2") (pintype "passive"))
      (node (ref "CC9") (pin "1") (pinfunction "1_1") (pintype "passive"))
      (node (ref "IC3") (pin "17") (pinfunction "VC9_17") (pintype "bidirectional"))
      (node (ref "IC3") (pin "18") (pinfunction "VC8_18") (pintype "bidirectional"))
      (node (ref "IC3") (pin "19") (pinfunction "VC7_19") (pintype "bidirectional"))
      (node (ref "RC9") (pin "2") (pinfunction "2_2") (pintype "passive"))
    )
    (net (code "57") (name "Net-(IC3-VC10)") (class "Default")
      (node (ref "CC10") (pin "1") (pinfunction "1_1") (pintype "passive"))
      (node (ref "D3") (pin "A") (pinfunction "A_A") (pintype "passive"))
      (node (ref "IC3") (pin "16") (pinfunction "VC10_16") (pintype "bidirectional"))
      (node (ref "RC10") (pin "2") (pinfunction "2_2") (pintype "passive"))
    )
    (net (code "58") (name "Net-(JP1-Pad1)") (class "Default")
      (node (ref "JP1") (pin "1") (pinfunction "1_1") (pintype "passive"))
      (node (ref "R42") (pin "1") (pinfunction "1_1") (pintype "passive"))
    )
    (net (code "59") (name "Net-(JP1-Pad2)") (class "Default")
      (node (ref "JP1") (pin "2") (pinfunction "2_2") (pintype "passive"))
      (node (ref "R41") (pin "1") (pinfunction "1_1") (pintype "passive"))
    )
    (net (code "60") (name "Net-(OC_SC_RED-PadC)") (class "Default")
      (node (ref "OC_SC_RED") (pin "C") (pinfunction "C_C") (pintype "passive"))
      (node (ref "R13") (pin "2") (pinfunction "2_2") (pintype "passive"))
    )
    (net (code "61") (name "Net-(OK_GRN-PadC)") (class "Default")
      (node (ref "OK_GRN") (pin "C") (pinfunction "C_C") (pintype "passive"))
      (node (ref "R11") (pin "2") (pinfunction "2_2") (pintype "passive"))
    )
    (net (code "62") (name "Net-(Q1-D)") (class "Default")
      (node (ref "C30") (pin "2") (pinfunction "2_2") (pintype "passive"))
      (node (ref "Q1") (pin "3") (pinfunction "D_3") (pintype "passive"))
      (node (ref "R1") (pin "1") (pinfunction "1_1") (pintype "passive"))
    )
    (net (code "63") (name "Net-(Q1-G)") (class "Default")
      (node (ref "Q1") (pin "1") (pinfunction "G_1") (pintype "passive"))
      (node (ref "R20") (pin "2") (pinfunction "2_2") (pintype "passive"))
    )
    (net (code "64") (name "Net-(Q2-D)") (class "Default")
      (node (ref "Q2") (pin "3") (pinfunction "D_3") (pintype "passive"))
      (node (ref "Q4") (pin "4") (pinfunction "G2_4") (pintype "bidirectional"))
      (node (ref "R25") (pin "1") (pinfunction "1_1") (pintype "passive"))
      (node (ref "U$3") (pin "2") (pinfunction "K1_2") (pintype "passive"))
    )
    (net (code "65") (name "Net-(Q2-G)") (class "Default")
      (node (ref "Q2") (pin "1") (pinfunction "G_1") (pintype "passive"))
      (node (ref "R28") (pin "2") (pinfunction "2_2") (pintype "passive"))
      (node (ref "R30") (pin "1") (pinfunction "1_1") (pintype "passive"))
    )
    (net (code "66") (name "Net-(Q3-D)") (class "Default")
      (node (ref "Q3") (pin "3") (pinfunction "D_3") (pintype "passive"))
      (node (ref "Q4") (pin "2") (pinfunction "G1_2") (pintype "bidirectional"))
      (node (ref "R10") (pin "1") (pinfunction "1_1") (pintype "passive"))
      (node (ref "U$3") (pin "1") (pinfunction "K2_1") (pintype "passive"))
    )
    (net (code "67") (name "Net-(Q3-G)") (class "Default")
      (node (ref "Q3") (pin "1") (pinfunction "G_1") (pintype "passive"))
      (node (ref "R29") (pin "1") (pinfunction "1_1") (pintype "passive"))
      (node (ref "R31") (pin "2") (pinfunction "2_2") (pintype "passive"))
    )
    (net (code "68") (name "Net-(Q4-D1_1)") (class "Default")
      (node (ref "MCB") (pin "4") (pinfunction "4_4") (pintype "passive"))
      (node (ref "Q4") (pin "5") (pinfunction "D2_1_5") (pintype "bidirectional"))
      (node (ref "Q4") (pin "6") (pinfunction "D2_2_6") (pintype "bidirectional"))
      (node (ref "Q4") (pin "7") (pinfunction "D1_1_7") (pintype "bidirectional"))
      (node (ref "Q4") (pin "8") (pinfunction "D1_2_8") (pintype "bidirectional"))
    )
    (net (code "69") (name "Net-(R6-Pad1)") (class "Default")
      (node (ref "R6") (pin "1") (pinfunction "1_1") (pintype "passive"))
      (node (ref "UART") (pin "1") (pinfunction "1_1") (pintype "passive"))
    )
    (net (code "70") (name "Net-(R7-Pad1)") (class "Default")
      (node (ref "R7") (pin "1") (pinfunction "1_1") (pintype "passive"))
      (node (ref "UART") (pin "2") (pinfunction "2_2") (pintype "passive"))
    )
    (net (code "71") (name "Net-(R12-Pad2)") (class "Default")
      (node (ref "R12") (pin "2") (pinfunction "2_2") (pintype "passive"))
      (node (ref "UV_OV_RED") (pin "C") (pinfunction "C_C") (pintype "passive"))
    )
    (net (code "72") (name "Net-(R22-Pad1)") (class "Default")
      (node (ref "R22") (pin "1") (pinfunction "1_1") (pintype "passive"))
      (node (ref "U$2") (pin "3") (pinfunction "P$2_3") (pintype "bidirectional"))
      (node (ref "U$2") (pin "4") (pinfunction "P$2_4") (pintype "bidirectional"))
    )
    (net (code "73") (name "unconnected-(IC1-ADC6-Pad19)") (class "Default")
      (node (ref "IC1") (pin "19") (pinfunction "ADC6_19") (pintype "bidirectional"))
    )
    (net (code "74") (name "unconnected-(IC1-ADC7-Pad22)") (class "Default")
      (node (ref "IC1") (pin "22") (pinfunction "ADC7_22") (pintype "bidirectional"))
    )
    (net (code "75") (name "unconnected-(IC1-PC0(ADC0)-Pad23)") (class "Default")
      (node (ref "IC1") (pin "23") (pinfunction "PC0(ADC0)_23") (pintype "bidirectional"))
    )
    (net (code "76") (name "unconnected-(IC1-PC1(ADC1)-Pad24)") (class "Default")
      (node (ref "IC1") (pin "24") (pinfunction "PC1(ADC1)_24") (pintype "bidirectional"))
    )
    (net (code "77") (name "unconnected-(IC1-PC2(ADC2)-Pad25)") (class "Default")
      (node (ref "IC1") (pin "25") (pinfunction "PC2(ADC2)_25") (pintype "bidirectional"))
    )
    (net (code "78") (name "unconnected-(IC1-PC3(ADC3)-Pad26)") (class "Default")
      (node (ref "IC1") (pin "26") (pinfunction "PC3(ADC3)_26") (pintype "bidirectional"))
    )
    (net (code "79") (name "unconnected-(IC1-PD3(INT1)-Pad1)") (class "Default")
      (node (ref "IC1") (pin "1") (pinfunction "PD3(INT1)_1") (pintype "bidirectional"))
    )
    (net (code "80") (name "unconnected-(IC1-PD4(XCK{slash}T0)-Pad2)") (class "Default")
      (node (ref "IC1") (pin "2") (pinfunction "PD4(XCK/T0)_2") (pintype "bidirectional"))
    )
    (net (code "81") (name "unconnected-(IC2-NC-Pad4)") (class "Default")
      (node (ref "IC2") (pin "4") (pinfunction "NC_4") (pintype "no_connect"))
    )
  )
)
